# MCU_Board.net
KiCad netlist of a schematic drawn in EAGLE
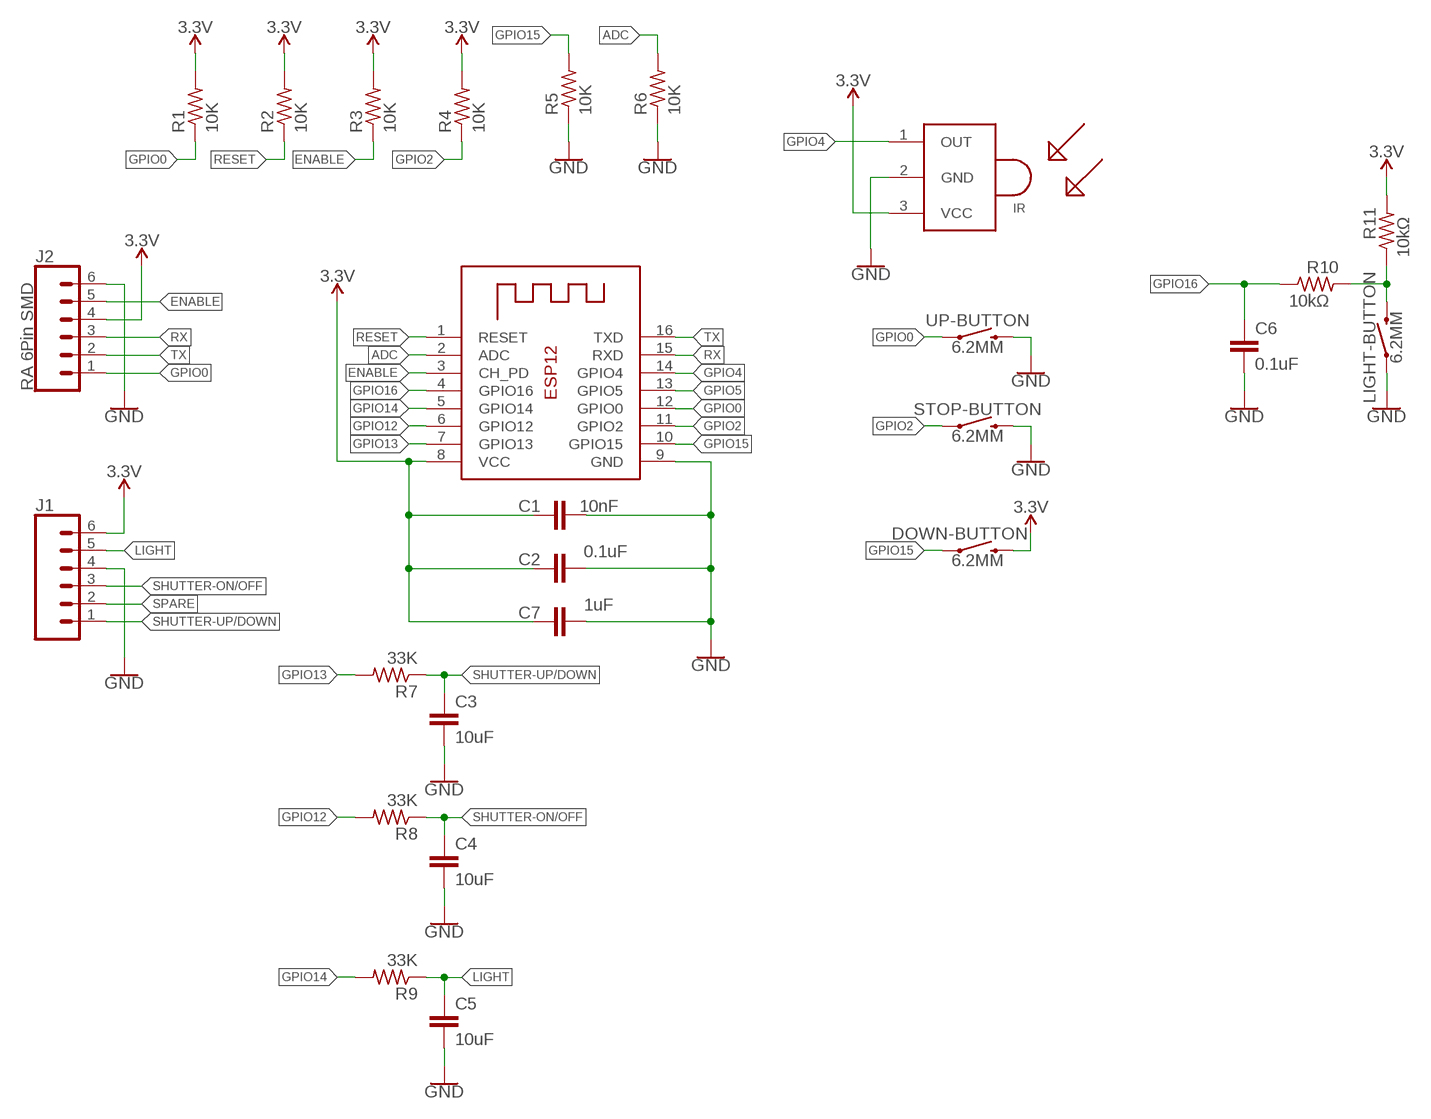
[diagram p0: schematic, sheet 1]

(export (version "E")
  (design (tool "Eeschema 10.0.6"))
  (components
    (comp (ref "C1")
      (value "10nF")
      (footprint "eagle-import:C0805")
      (libsource (lib "eagle-import") (part "C-EUC0805"))
    )
    (comp (ref "C2")
      (value "0.1uF")
      (footprint "eagle-import:C0805")
      (libsource (lib "eagle-import") (part "C-EUC0805"))
    )
    (comp (ref "C3")
      (value "10uF")
      (footprint "eagle-import:C0805")
      (libsource (lib "eagle-import") (part "C-EUC0805"))
    )
    (comp (ref "C4")
      (value "10uF")
      (footprint "eagle-import:C0805")
      (libsource (lib "eagle-import") (part "C-EUC0805"))
    )
    (comp (ref "C5")
      (value "10uF")
      (footprint "eagle-import:C0805")
      (libsource (lib "eagle-import") (part "C-EUC0805"))
    )
    (comp (ref "C6")
      (value "0.1uF")
      (footprint "eagle-import:C0805")
      (libsource (lib "eagle-import") (part "C-EUC0805"))
    )
    (comp (ref "C7")
      (value "1uF")
      (footprint "eagle-import:C0805")
      (libsource (lib "eagle-import") (part "C-EUC0805"))
    )
    (comp (ref "DOWN-BUTTON")
      (value "6.2MM")
      (footprint "eagle-import:TACTILE_SWITCH_SMD_6.2MM_TALL")
      (libsource (lib "eagle-import") (part "MOMENTARY-SWITCH-SPST-SMD-6.2MM-TALL"))
    )
    (comp (ref "IR")
      (value "TSOP382")
      (footprint "eagle-import:TSOP382__-VERTICAL")
      (libsource (lib "eagle-import") (part "TSOP382"))
    )
    (comp (ref "J1")
      (value "CONN_06LOCK")
      (footprint "eagle-import:1X06_LOCK")
      (libsource (lib "eagle-import") (part "CONN_06LOCK"))
    )
    (comp (ref "J2")
      (value "RA 6Pin SMD")
      (footprint "eagle-import:1X06-SMD_RA_MALE")
      (libsource (lib "eagle-import") (part "CONN_06SMD"))
    )
    (comp (ref "LIGHT-BUTTON")
      (value "6.2MM")
      (footprint "eagle-import:TACTILE_SWITCH_SMD_6.2MM_TALL")
      (libsource (lib "eagle-import") (part "MOMENTARY-SWITCH-SPST-SMD-6.2MM-TALL"))
    )
    (comp (ref "R1")
      (value "10K")
      (footprint "eagle-import:R0805")
      (libsource (lib "eagle-import") (part "rcl_334_R-US_R0805"))
    )
    (comp (ref "R2")
      (value "10K")
      (footprint "eagle-import:R0805")
      (libsource (lib "eagle-import") (part "rcl_334_R-US_R0805"))
    )
    (comp (ref "R3")
      (value "10K")
      (footprint "eagle-import:R0805")
      (libsource (lib "eagle-import") (part "rcl_334_R-US_R0805"))
    )
    (comp (ref "R4")
      (value "10K")
      (footprint "eagle-import:R0805")
      (libsource (lib "eagle-import") (part "rcl_334_R-US_R0805"))
    )
    (comp (ref "R5")
      (value "10K")
      (footprint "eagle-import:R0805")
      (libsource (lib "eagle-import") (part "rcl_334_R-US_R0805"))
    )
    (comp (ref "R6")
      (value "10K")
      (footprint "eagle-import:R0805")
      (libsource (lib "eagle-import") (part "rcl_334_R-US_R0805"))
    )
    (comp (ref "R7")
      (value "33K")
      (footprint "eagle-import:R0805")
      (libsource (lib "eagle-import") (part "rcl_334_R-US_R0805"))
    )
    (comp (ref "R8")
      (value "33K")
      (footprint "eagle-import:R0805")
      (libsource (lib "eagle-import") (part "rcl_334_R-US_R0805"))
    )
    (comp (ref "R9")
      (value "33K")
      (footprint "eagle-import:R0805")
      (libsource (lib "eagle-import") (part "rcl_334_R-US_R0805"))
    )
    (comp (ref "R10")
      (value "10kΩ")
      (footprint "eagle-import:R0805")
      (libsource (lib "eagle-import") (part "R-US_R0805"))
    )
    (comp (ref "R11")
      (value "10kΩ")
      (footprint "eagle-import:R0805")
      (libsource (lib "eagle-import") (part "R-US_R0805"))
    )
    (comp (ref "STOP-BUTTON")
      (value "6.2MM")
      (footprint "eagle-import:TACTILE_SWITCH_SMD_6.2MM_TALL")
      (libsource (lib "eagle-import") (part "MOMENTARY-SWITCH-SPST-SMD-6.2MM-TALL"))
    )
    (comp (ref "UP-BUTTON")
      (value "6.2MM")
      (footprint "eagle-import:TACTILE_SWITCH_SMD_6.2MM_TALL")
      (libsource (lib "eagle-import") (part "MOMENTARY-SWITCH-SPST-SMD-6.2MM-TALL"))
    )
    (comp (ref "X1")
      (value "ESP-12")
      (footprint "eagle-import:ESP-12")
      (libsource (lib "eagle-import") (part "ESP-12"))
    )
  )
  (nets
    (net (code "1") (name "3.3V") (class "Default")
      (node (ref "C1") (pin "1") (pinfunction "1_1") (pintype "passive"))
      (node (ref "C2") (pin "1") (pinfunction "1_1") (pintype "passive"))
      (node (ref "C7") (pin "1") (pinfunction "1_1") (pintype "passive"))
      (node (ref "DOWN-BUTTON") (pin "B2") (pinfunction "2_B2") (pintype "passive"))
      (node (ref "IR") (pin "3") (pinfunction "VCC_3") (pintype "power_in"))
      (node (ref "J1") (pin "6") (pinfunction "6_6") (pintype "passive"))
      (node (ref "J2") (pin "4") (pinfunction "4_4") (pintype "passive"))
      (node (ref "R1") (pin "2") (pinfunction "2_2") (pintype "passive"))
      (node (ref "R11") (pin "2") (pinfunction "2_2") (pintype "passive"))
      (node (ref "R2") (pin "2") (pinfunction "2_2") (pintype "passive"))
      (node (ref "R3") (pin "2") (pinfunction "2_2") (pintype "passive"))
      (node (ref "R4") (pin "2") (pinfunction "2_2") (pintype "passive"))
      (node (ref "X1") (pin "8") (pinfunction "VCC_8") (pintype "power_in"))
    )
    (net (code "2") (name "ADC") (class "Default")
      (node (ref "R6") (pin "2") (pinfunction "2_2") (pintype "passive"))
      (node (ref "X1") (pin "2") (pinfunction "ADC_2") (pintype "passive"))
    )
    (net (code "3") (name "ENABLE") (class "Default")
      (node (ref "J2") (pin "5") (pinfunction "5_5") (pintype "passive"))
      (node (ref "R3") (pin "1") (pinfunction "1_1") (pintype "passive"))
      (node (ref "X1") (pin "3") (pinfunction "CH_PD_3") (pintype "input"))
    )
    (net (code "4") (name "GND") (class "Default")
      (node (ref "C1") (pin "2") (pinfunction "2_2") (pintype "passive"))
      (node (ref "C2") (pin "2") (pinfunction "2_2") (pintype "passive"))
      (node (ref "C3") (pin "2") (pinfunction "2_2") (pintype "passive"))
      (node (ref "C4") (pin "2") (pinfunction "2_2") (pintype "passive"))
      (node (ref "C5") (pin "2") (pinfunction "2_2") (pintype "passive"))
      (node (ref "C6") (pin "2") (pinfunction "2_2") (pintype "passive"))
      (node (ref "C7") (pin "2") (pinfunction "2_2") (pintype "passive"))
      (node (ref "IR") (pin "2") (pinfunction "GND_2") (pintype "power_in"))
      (node (ref "J1") (pin "4") (pinfunction "4_4") (pintype "passive"))
      (node (ref "J2") (pin "6") (pinfunction "6_6") (pintype "passive"))
      (node (ref "LIGHT-BUTTON") (pin "A2") (pinfunction "1_A2") (pintype "passive"))
      (node (ref "R5") (pin "1") (pinfunction "1_1") (pintype "passive"))
      (node (ref "R6") (pin "1") (pinfunction "1_1") (pintype "passive"))
      (node (ref "STOP-BUTTON") (pin "B2") (pinfunction "2_B2") (pintype "passive"))
      (node (ref "UP-BUTTON") (pin "B2") (pinfunction "2_B2") (pintype "passive"))
      (node (ref "X1") (pin "9") (pinfunction "GND_9") (pintype "power_in"))
    )
    (net (code "5") (name "GPIO0") (class "Default")
      (node (ref "J2") (pin "1") (pinfunction "1_1") (pintype "passive"))
      (node (ref "R1") (pin "1") (pinfunction "1_1") (pintype "passive"))
      (node (ref "UP-BUTTON") (pin "A2") (pinfunction "1_A2") (pintype "passive"))
      (node (ref "X1") (pin "12") (pinfunction "GPIO0_12") (pintype "bidirectional"))
    )
    (net (code "6") (name "GPIO2") (class "Default")
      (node (ref "R4") (pin "1") (pinfunction "1_1") (pintype "passive"))
      (node (ref "STOP-BUTTON") (pin "A2") (pinfunction "1_A2") (pintype "passive"))
      (node (ref "X1") (pin "11") (pinfunction "GPIO2_11") (pintype "bidirectional"))
    )
    (net (code "7") (name "GPIO4") (class "Default")
      (node (ref "IR") (pin "1") (pinfunction "OUT_1") (pintype "bidirectional"))
      (node (ref "X1") (pin "14") (pinfunction "GPIO4_14") (pintype "bidirectional"))
    )
    (net (code "8") (name "GPIO5") (class "Default")
      (node (ref "X1") (pin "13") (pinfunction "GPIO5_13") (pintype "bidirectional"))
    )
    (net (code "9") (name "GPIO12") (class "Default")
      (node (ref "R8") (pin "2") (pinfunction "2_2") (pintype "passive"))
      (node (ref "X1") (pin "6") (pinfunction "GPIO12_6") (pintype "bidirectional"))
    )
    (net (code "10") (name "GPIO13") (class "Default")
      (node (ref "R7") (pin "2") (pinfunction "2_2") (pintype "passive"))
      (node (ref "X1") (pin "7") (pinfunction "GPIO13_7") (pintype "bidirectional"))
    )
    (net (code "11") (name "GPIO14") (class "Default")
      (node (ref "R9") (pin "2") (pinfunction "2_2") (pintype "passive"))
      (node (ref "X1") (pin "5") (pinfunction "GPIO14_5") (pintype "bidirectional"))
    )
    (net (code "12") (name "GPIO15") (class "Default")
      (node (ref "DOWN-BUTTON") (pin "A2") (pinfunction "1_A2") (pintype "passive"))
      (node (ref "R5") (pin "2") (pinfunction "2_2") (pintype "passive"))
      (node (ref "X1") (pin "10") (pinfunction "GPIO15_10") (pintype "bidirectional"))
    )
    (net (code "13") (name "GPIO16") (class "Default")
      (node (ref "C6") (pin "1") (pinfunction "1_1") (pintype "passive"))
      (node (ref "R10") (pin "1") (pinfunction "1_1") (pintype "passive"))
      (node (ref "X1") (pin "4") (pinfunction "GPIO16_4") (pintype "bidirectional"))
    )
    (net (code "14") (name "LIGHT") (class "Default")
      (node (ref "C5") (pin "1") (pinfunction "1_1") (pintype "passive"))
      (node (ref "J1") (pin "5") (pinfunction "5_5") (pintype "passive"))
      (node (ref "R9") (pin "1") (pinfunction "1_1") (pintype "passive"))
    )
    (net (code "15") (name "Net-(LIGHT-BUTTON-2)") (class "Default")
      (node (ref "LIGHT-BUTTON") (pin "B2") (pinfunction "2_B2") (pintype "passive"))
      (node (ref "R10") (pin "2") (pinfunction "2_2") (pintype "passive"))
      (node (ref "R11") (pin "1") (pinfunction "1_1") (pintype "passive"))
    )
    (net (code "16") (name "RESET") (class "Default")
      (node (ref "R2") (pin "1") (pinfunction "1_1") (pintype "passive"))
      (node (ref "X1") (pin "1") (pinfunction "RESET_1") (pintype "input"))
    )
    (net (code "17") (name "RX") (class "Default")
      (node (ref "J2") (pin "3") (pinfunction "3_3") (pintype "passive"))
      (node (ref "X1") (pin "15") (pinfunction "RXD_15") (pintype "input"))
    )
    (net (code "18") (name "SHUTTER-ON{slash}OFF") (class "Default")
      (node (ref "C4") (pin "1") (pinfunction "1_1") (pintype "passive"))
      (node (ref "J1") (pin "3") (pinfunction "3_3") (pintype "passive"))
      (node (ref "R8") (pin "1") (pinfunction "1_1") (pintype "passive"))
    )
    (net (code "19") (name "SHUTTER-UP{slash}DOWN") (class "Default")
      (node (ref "C3") (pin "1") (pinfunction "1_1") (pintype "passive"))
      (node (ref "J1") (pin "1") (pinfunction "1_1") (pintype "passive"))
      (node (ref "R7") (pin "1") (pinfunction "1_1") (pintype "passive"))
    )
    (net (code "20") (name "SPARE") (class "Default")
      (node (ref "J1") (pin "2") (pinfunction "2_2") (pintype "passive"))
    )
    (net (code "21") (name "TX") (class "Default")
      (node (ref "J2") (pin "2") (pinfunction "2_2") (pintype "passive"))
      (node (ref "X1") (pin "16") (pinfunction "TXD_16") (pintype "output"))
    )
  )
)
